# InverterControl.net
KiCad netlist of a schematic drawn in EAGLE
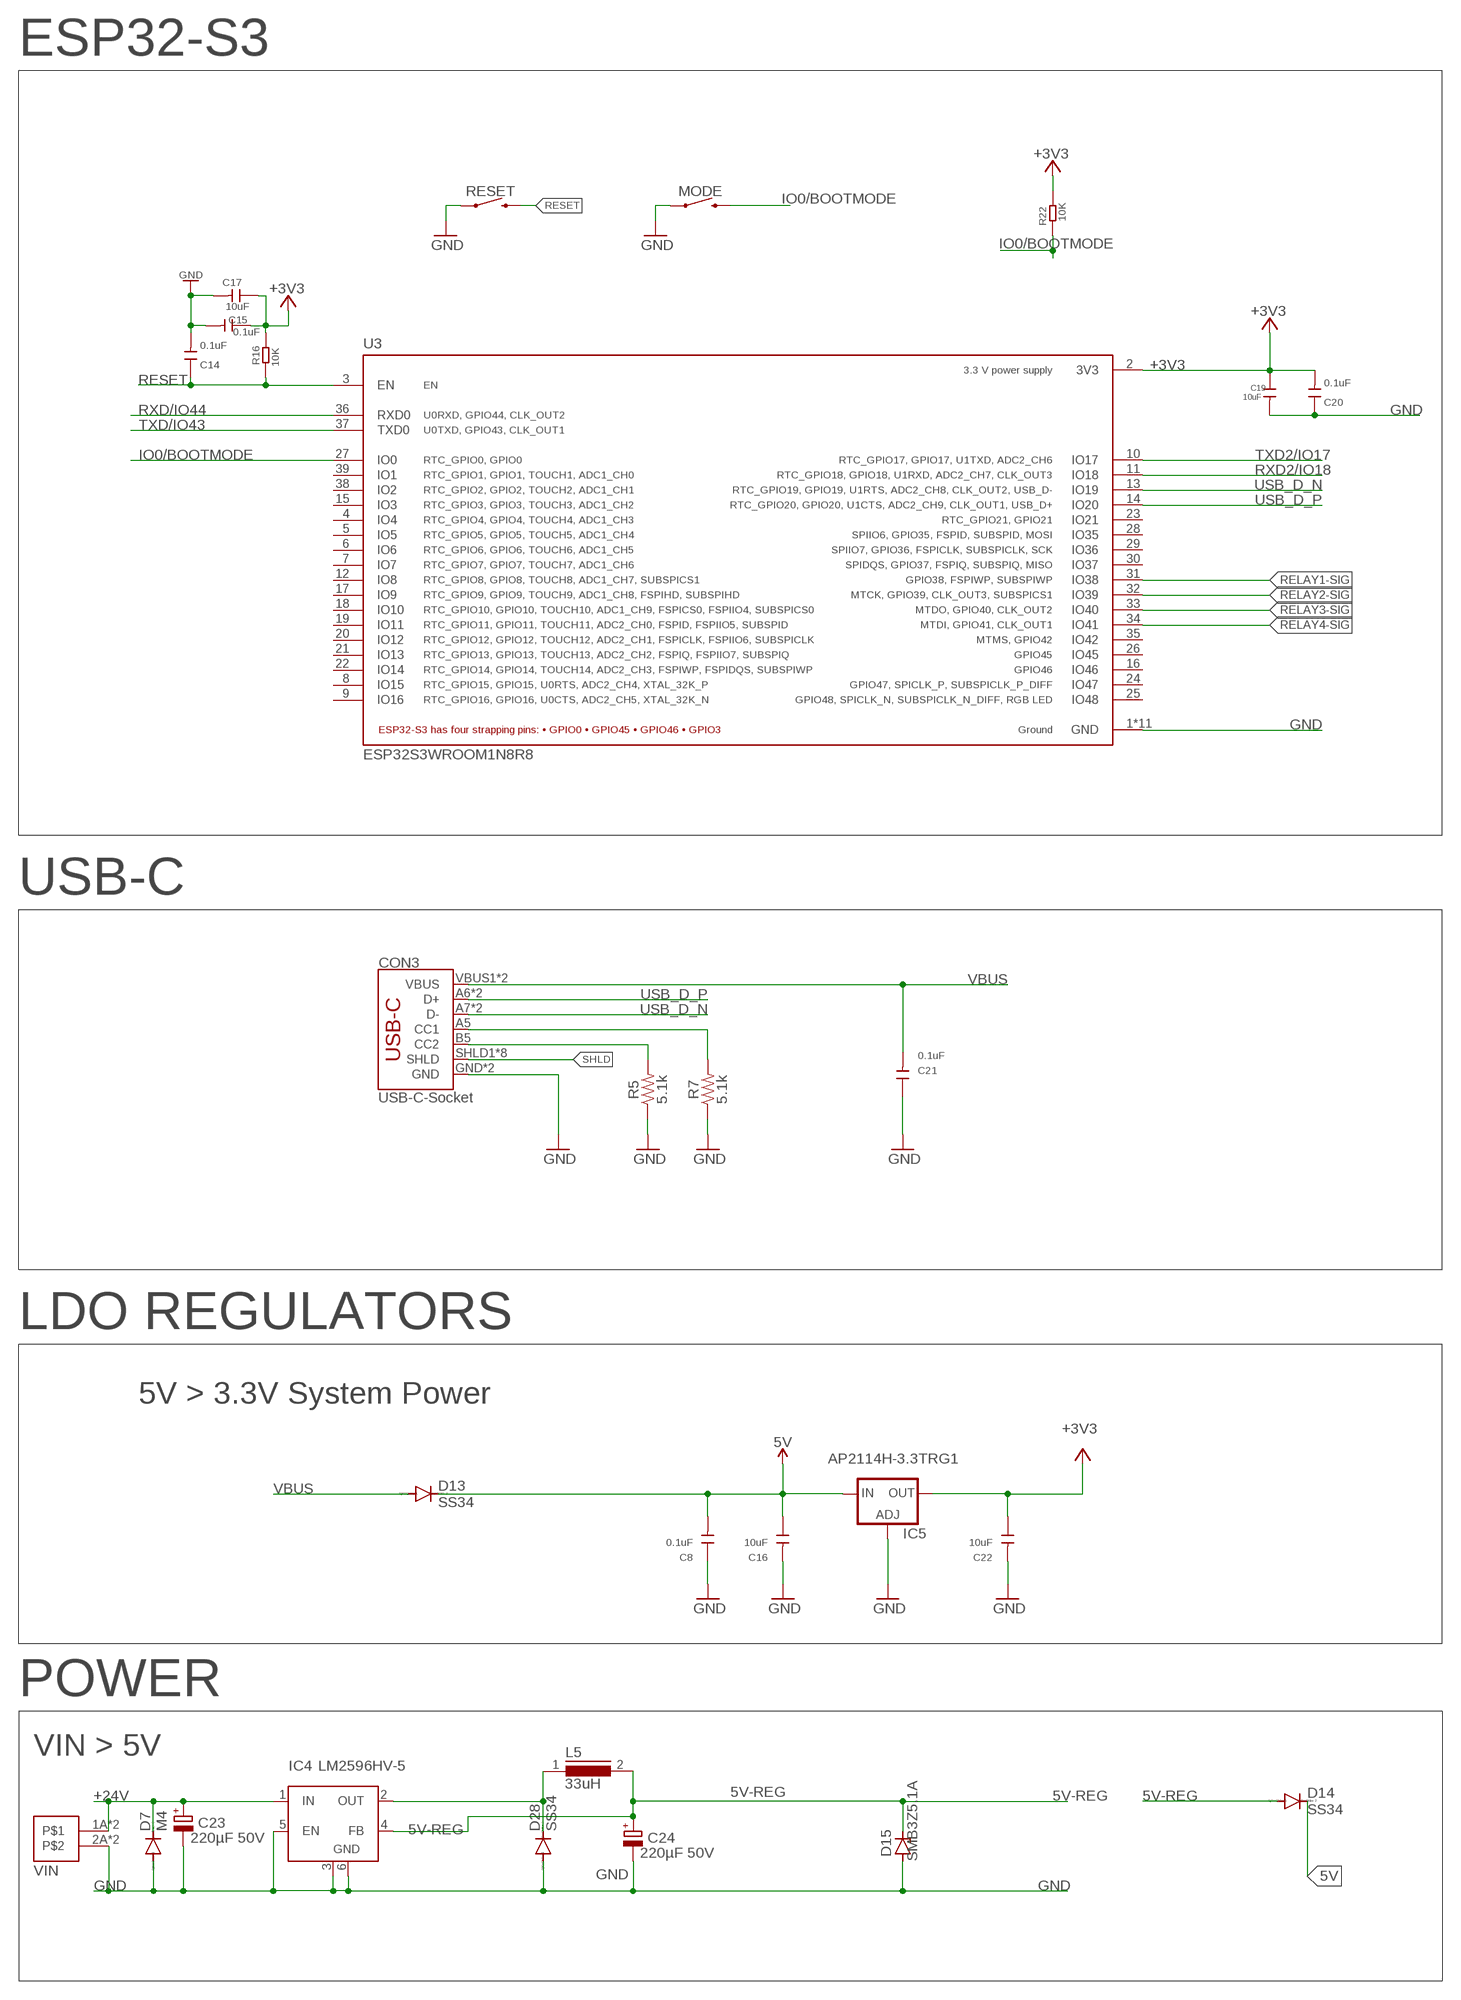
[diagram p0: schematic, sheet 1, part 1 of 2]
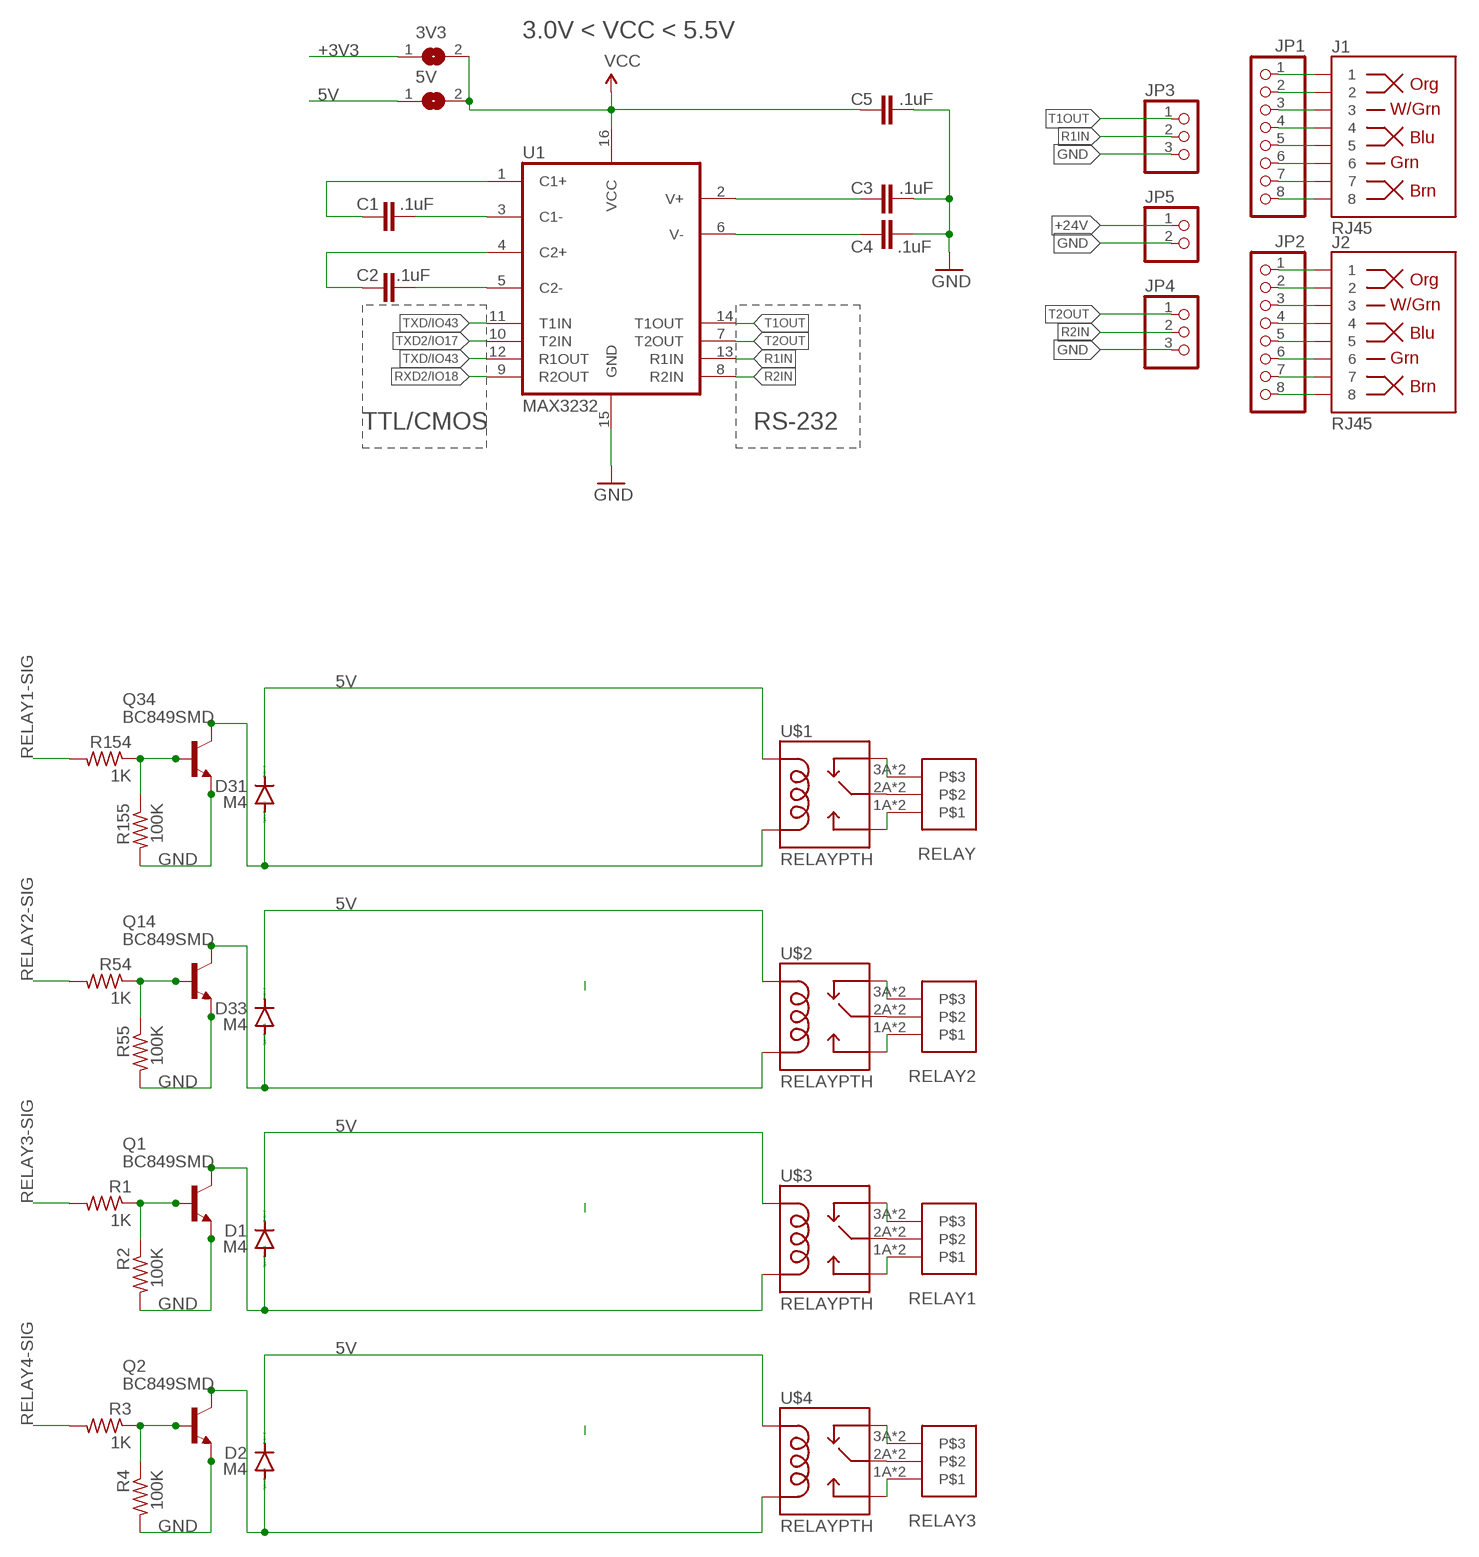
[diagram p1: schematic, sheet 1, part 2 of 2]

(export (version "E")
  (design (tool "Eeschema 10.0.6"))
  (components
    (comp (ref "3V3") (value "SJ") (footprint "eagle-import:SJ") (libsource (lib "eagle-import") (part "SJ")))
    (comp (ref "5V") (value "SJ") (footprint "eagle-import:SJ") (libsource (lib "eagle-import") (part "SJ")))
    (comp (ref "C1")
      (value ".1uF")
      (footprint "eagle-import:0603-CAP")
      (fields (field (name "PROD_ID") "CAP-00810"))
      (libsource (lib "eagle-import") (part "0.1UF-25V(+80/-20%)(0603)"))
    )
    (comp (ref "C2")
      (value ".1uF")
      (footprint "eagle-import:0603-CAP")
      (fields (field (name "PROD_ID") "CAP-00810"))
      (libsource (lib "eagle-import") (part "0.1UF-25V(+80/-20%)(0603)"))
    )
    (comp (ref "C3")
      (value ".1uF")
      (footprint "eagle-import:0603-CAP")
      (fields (field (name "PROD_ID") "CAP-00810"))
      (libsource (lib "eagle-import") (part "0.1UF-25V(+80/-20%)(0603)"))
    )
    (comp (ref "C4")
      (value ".1uF")
      (footprint "eagle-import:0603-CAP")
      (fields (field (name "PROD_ID") "CAP-00810"))
      (libsource (lib "eagle-import") (part "0.1UF-25V(+80/-20%)(0603)"))
    )
    (comp (ref "C5")
      (value ".1uF")
      (footprint "eagle-import:0603-CAP")
      (fields (field (name "PROD_ID") "CAP-00810"))
      (libsource (lib "eagle-import") (part "0.1UF-25V(+80/-20%)(0603)"))
    )
    (comp (ref "C8")
      (value "0.1uF")
      (footprint "eagle-import:DISCRETE_C1206")
      (libsource (lib "eagle-import") (part "DISCRETE_C-1206"))
    )
    (comp (ref "C14")
      (value "0.1uF")
      (footprint "eagle-import:DISCRETE_C1206")
      (libsource (lib "eagle-import") (part "DISCRETE_C-1206"))
    )
    (comp (ref "C15")
      (value "0.1uF")
      (footprint "eagle-import:DISCRETE_C1206")
      (libsource (lib "eagle-import") (part "DISCRETE_C-1206"))
    )
    (comp (ref "C16")
      (value "10uF")
      (footprint "eagle-import:C1206")
      (libsource (lib "eagle-import") (part "C-1206"))
    )
    (comp (ref "C17")
      (value "10uF")
      (footprint "eagle-import:DISCRETE_C1206")
      (libsource (lib "eagle-import") (part "DISCRETE_C-1206"))
    )
    (comp (ref "C19")
      (value "10uF")
      (footprint "eagle-import:C1206")
      (libsource (lib "eagle-import") (part "C-1206"))
    )
    (comp (ref "C20")
      (value "0.1uF")
      (footprint "eagle-import:DISCRETE_C1206")
      (libsource (lib "eagle-import") (part "DISCRETE_C-1206"))
    )
    (comp (ref "C21")
      (value "0.1uF")
      (footprint "eagle-import:DISCRETE_C1206")
      (libsource (lib "eagle-import") (part "DISCRETE_C-1206"))
    )
    (comp (ref "C22")
      (value "10uF")
      (footprint "eagle-import:C1206")
      (libsource (lib "eagle-import") (part "C-1206"))
    )
    (comp (ref "C23")
      (value "220µF 50V")
      (footprint "eagle-import:PANASONIC_E")
      (libsource (lib "eagle-import") (part "CPOL-EUE"))
    )
    (comp (ref "C24")
      (value "220µF 50V")
      (footprint "eagle-import:PANASONIC_E")
      (libsource (lib "eagle-import") (part "CPOL-EUE"))
    )
    (comp (ref "CON3")
      (value "USB-C-Socket")
      (footprint "eagle-import:USB-C-16P")
      (libsource (lib "eagle-import") (part "USB_C16PIN"))
    )
    (comp (ref "D1")
      (value "M4")
      (footprint "eagle-import:DO-214AC")
      (libsource (lib "eagle-import") (part "DIODE-DO-214AC"))
    )
    (comp (ref "D2")
      (value "M4")
      (footprint "eagle-import:DO-214AC")
      (libsource (lib "eagle-import") (part "DIODE-DO-214AC"))
    )
    (comp (ref "D7")
      (value "M4")
      (footprint "eagle-import:DO-214AC")
      (libsource (lib "eagle-import") (part "DIODE-DO-214AC"))
    )
    (comp (ref "D13")
      (value "SS34")
      (footprint "eagle-import:DO-214AC")
      (libsource (lib "eagle-import") (part "DIODE-DO-214AC"))
    )
    (comp (ref "D14")
      (value "SS34")
      (footprint "eagle-import:SMB")
      (libsource (lib "eagle-import") (part "DIODE-SMB"))
    )
    (comp (ref "D15")
      (value "SMB3Z5.1A")
      (footprint "eagle-import:SMB")
      (libsource (lib "eagle-import") (part "ZENER-DIODESMB"))
    )
    (comp (ref "D28")
      (value "SS34")
      (footprint "eagle-import:SMB")
      (libsource (lib "eagle-import") (part "DIODE-SMB"))
    )
    (comp (ref "D31")
      (value "M4")
      (footprint "eagle-import:DO-214AC")
      (libsource (lib "eagle-import") (part "DIODE-DO-214AC"))
    )
    (comp (ref "D33")
      (value "M4")
      (footprint "eagle-import:DO-214AC")
      (libsource (lib "eagle-import") (part "DIODE-DO-214AC"))
    )
    (comp (ref "IC4")
      (value "LM2596HV-5")
      (footprint "eagle-import:TO263-5")
      (libsource (lib "eagle-import") (part "LM2596S"))
    )
    (comp (ref "IC5")
      (value "AP2114H-3.3TRG1")
      (footprint "eagle-import:SOT223")
      (libsource (lib "eagle-import") (part "LD117A?S33TR"))
    )
    (comp (ref "J1")
      (value "RJ45")
      (footprint "eagle-import:RJ45-8")
      (libsource (lib "eagle-import") (part "RJ45-8"))
    )
    (comp (ref "J2")
      (value "RJ45")
      (footprint "eagle-import:RJ45-8")
      (libsource (lib "eagle-import") (part "RJ45-8"))
    )
    (comp (ref "JP1")
      (value "PINHD-1X8")
      (footprint "eagle-import:1X08")
      (libsource (lib "eagle-import") (part "PINHD-1X8"))
    )
    (comp (ref "JP2")
      (value "PINHD-1X8")
      (footprint "eagle-import:1X08")
      (libsource (lib "eagle-import") (part "PINHD-1X8"))
    )
    (comp (ref "JP3")
      (value "PINHD-1X3")
      (footprint "eagle-import:1X03")
      (libsource (lib "eagle-import") (part "PINHD-1X3"))
    )
    (comp (ref "JP4")
      (value "PINHD-1X3")
      (footprint "eagle-import:1X03")
      (libsource (lib "eagle-import") (part "PINHD-1X3"))
    )
    (comp (ref "JP5")
      (value "PINHD-1X2")
      (footprint "eagle-import:1X02")
      (libsource (lib "eagle-import") (part "PINHD-1X2"))
    )
    (comp (ref "L5")
      (value "33uH")
      (footprint "eagle-import:DR127")
      (libsource (lib "eagle-import") (part "DR127"))
    )
    (comp (ref "MODE")
      (value "MOMENTARY-SWITCH-SPST-PTH-6.0MM")
      (footprint "eagle-import:TACTILE_SWITCH_PTH_6.0MM")
      (libsource (lib "eagle-import") (part "MOMENTARY-SWITCH-SPST-PTH-6.0MM"))
    )
    (comp (ref "Q1")
      (value "BC849SMD")
      (footprint "eagle-import:SOT23-BEC")
      (libsource (lib "eagle-import") (part "BC849SMD"))
    )
    (comp (ref "Q2")
      (value "BC849SMD")
      (footprint "eagle-import:SOT23-BEC")
      (libsource (lib "eagle-import") (part "BC849SMD"))
    )
    (comp (ref "Q14")
      (value "BC849SMD")
      (footprint "eagle-import:SOT23-BEC")
      (libsource (lib "eagle-import") (part "BC849SMD"))
    )
    (comp (ref "Q34")
      (value "BC849SMD")
      (footprint "eagle-import:SOT23-BEC")
      (libsource (lib "eagle-import") (part "BC849SMD"))
    )
    (comp (ref "R1")
      (value "1K")
      (footprint "eagle-import:R1206")
      (libsource (lib "eagle-import") (part "R-US_R1206"))
    )
    (comp (ref "R2")
      (value "100K")
      (footprint "eagle-import:R1206")
      (libsource (lib "eagle-import") (part "R-US_R1206"))
    )
    (comp (ref "R3")
      (value "1K")
      (footprint "eagle-import:R1206")
      (libsource (lib "eagle-import") (part "R-US_R1206"))
    )
    (comp (ref "R4")
      (value "100K")
      (footprint "eagle-import:R1206")
      (libsource (lib "eagle-import") (part "R-US_R1206"))
    )
    (comp (ref "R5")
      (value "5.1k")
      (footprint "eagle-import:0603@1")
      (libsource (lib "eagle-import") (part "5.1KOHM5.1KOHM-0603-1/10W-1%"))
    )
    (comp (ref "R7")
      (value "5.1k")
      (footprint "eagle-import:0603@1")
      (libsource (lib "eagle-import") (part "5.1KOHM5.1KOHM-0603-1/10W-1%"))
    )
    (comp (ref "R16")
      (value "10K")
      (footprint "eagle-import:R1206")
      (libsource (lib "eagle-import") (part "R-1206"))
    )
    (comp (ref "R22")
      (value "10K")
      (footprint "eagle-import:R1206")
      (libsource (lib "eagle-import") (part "R-1206"))
    )
    (comp (ref "R54")
      (value "1K")
      (footprint "eagle-import:R1206")
      (libsource (lib "eagle-import") (part "R-US_R1206"))
    )
    (comp (ref "R55")
      (value "100K")
      (footprint "eagle-import:R1206")
      (libsource (lib "eagle-import") (part "R-US_R1206"))
    )
    (comp (ref "R154")
      (value "1K")
      (footprint "eagle-import:R1206")
      (libsource (lib "eagle-import") (part "R-US_R1206"))
    )
    (comp (ref "R155")
      (value "100K")
      (footprint "eagle-import:R1206")
      (libsource (lib "eagle-import") (part "R-US_R1206"))
    )
    (comp (ref "RELAY")
      (value "WJ212R-THR-3.5-3")
      (footprint "eagle-import:WJ212R-THR-3.5-3")
      (libsource (lib "eagle-import") (part "WJ212R-THR-3.5-3"))
    )
    (comp (ref "RELAY1")
      (value "WJ212R-THR-3.5-3")
      (footprint "eagle-import:WJ212R-THR-3.5-3")
      (libsource (lib "eagle-import") (part "WJ212R-THR-3.5-3"))
    )
    (comp (ref "RELAY2")
      (value "WJ212R-THR-3.5-3")
      (footprint "eagle-import:WJ212R-THR-3.5-3")
      (libsource (lib "eagle-import") (part "WJ212R-THR-3.5-3"))
    )
    (comp (ref "RELAY3")
      (value "WJ212R-THR-3.5-3")
      (footprint "eagle-import:WJ212R-THR-3.5-3")
      (libsource (lib "eagle-import") (part "WJ212R-THR-3.5-3"))
    )
    (comp (ref "RESET")
      (value "MOMENTARY-SWITCH-SPST-PTH-6.0MM")
      (footprint "eagle-import:TACTILE_SWITCH_PTH_6.0MM")
      (libsource (lib "eagle-import") (part "MOMENTARY-SWITCH-SPST-PTH-6.0MM"))
    )
    (comp (ref "U$1")
      (value "RELAYPTH")
      (footprint "eagle-import:SRD-05VDC-SL-C")
      (libsource (lib "eagle-import") (part "RELAYPTH"))
    )
    (comp (ref "U$2")
      (value "RELAYPTH")
      (footprint "eagle-import:SRD-05VDC-SL-C")
      (libsource (lib "eagle-import") (part "RELAYPTH"))
    )
    (comp (ref "U$3")
      (value "RELAYPTH")
      (footprint "eagle-import:SRD-05VDC-SL-C")
      (libsource (lib "eagle-import") (part "RELAYPTH"))
    )
    (comp (ref "U$4")
      (value "RELAYPTH")
      (footprint "eagle-import:SRD-05VDC-SL-C")
      (libsource (lib "eagle-import") (part "RELAYPTH"))
    )
    (comp (ref "U1")
      (value "MAX3232")
      (footprint "eagle-import:SO016")
      (libsource (lib "eagle-import") (part "MAX232SOIC16"))
    )
    (comp (ref "U3")
      (value "ESP32S3WROOM1N8R8")
      (footprint "eagle-import:XCVR_ESP32S3WROOM1N8R8")
      (fields (field (name "MF") "Espressif Systems"))
      (libsource (lib "eagle-import") (part "ESP32S3WROOM1N8R8"))
    )
    (comp (ref "VIN")
      (value "WJ212R-THR-3.5-2")
      (footprint "eagle-import:WJ212R-THR-3.5-2")
      (libsource (lib "eagle-import") (part "WJ212R-THR-3.5-2"))
    )
  )
  (nets
    (net (code "1") (name "+3V3") (class "Default")
      (node (ref "3V3") (pin "1") (pinfunction "1_1") (pintype "passive"))
      (node (ref "C15") (pin "1") (pinfunction "1_1") (pintype "passive"))
      (node (ref "C17") (pin "1") (pinfunction "1_1") (pintype "passive"))
      (node (ref "C19") (pin "1") (pinfunction "1_1") (pintype "passive"))
      (node (ref "C20") (pin "2") (pinfunction "2_2") (pintype "passive"))
      (node (ref "C22") (pin "1") (pinfunction "1_1") (pintype "passive"))
      (node (ref "IC5") (pin "4") (pinfunction "OUT_4") (pintype "passive"))
      (node (ref "R16") (pin "2") (pinfunction "2_2") (pintype "passive"))
      (node (ref "R22") (pin "2") (pinfunction "2_2") (pintype "passive"))
      (node (ref "U3") (pin "2") (pinfunction "3V3_2") (pintype "power_in"))
    )
    (net (code "2") (name "+24V") (class "Default")
      (node (ref "C23") (pin "+") (pinfunction "+_+") (pintype "passive"))
      (node (ref "D7") (pin "C") (pinfunction "C_C") (pintype "passive"))
      (node (ref "IC4") (pin "1") (pinfunction "IN_1") (pintype "input"))
      (node (ref "JP5") (pin "1") (pinfunction "1_1") (pintype "passive"))
      (node (ref "VIN") (pin "1A") (pinfunction "P$1_1A") (pintype "bidirectional"))
      (node (ref "VIN") (pin "1B") (pinfunction "P$1_1B") (pintype "bidirectional"))
    )
    (net (code "3") (name "/5V-REG") (class "Default")
      (node (ref "C24") (pin "+") (pinfunction "+_+") (pintype "passive"))
      (node (ref "D14") (pin "A") (pinfunction "A_A") (pintype "passive"))
      (node (ref "D15") (pin "C") (pinfunction "C_C") (pintype "passive"))
      (node (ref "IC4") (pin "4") (pinfunction "FB_4") (pintype "input"))
      (node (ref "L5") (pin "2") (pinfunction "2_2") (pintype "passive"))
    )
    (net (code "4") (name "/IO0{slash}BOOTMODE") (class "Default")
      (node (ref "MODE") (pin "3") (pinfunction "2_3") (pintype "passive"))
      (node (ref "R22") (pin "1") (pinfunction "1_1") (pintype "passive"))
      (node (ref "U3") (pin "27") (pinfunction "IO0_27") (pintype "bidirectional"))
    )
    (net (code "5") (name "/RXD{slash}IO44") (class "Default")
      (node (ref "U3") (pin "36") (pinfunction "RXD0_36") (pintype "bidirectional"))
    )
    (net (code "6") (name "/USB_D_N") (class "Default")
      (node (ref "CON3") (pin "A7") (pinfunction "D-_A7") (pintype "bidirectional"))
      (node (ref "CON3") (pin "B7") (pinfunction "D-_B7") (pintype "bidirectional"))
      (node (ref "U3") (pin "13") (pinfunction "IO19_13") (pintype "bidirectional"))
    )
    (net (code "7") (name "/USB_D_P") (class "Default")
      (node (ref "CON3") (pin "A6") (pinfunction "D+_A6") (pintype "bidirectional"))
      (node (ref "CON3") (pin "B6") (pinfunction "D+_B6") (pintype "bidirectional"))
      (node (ref "U3") (pin "14") (pinfunction "IO20_14") (pintype "bidirectional"))
    )
    (net (code "8") (name "/VBUS") (class "Default")
      (node (ref "C21") (pin "2") (pinfunction "2_2") (pintype "passive"))
      (node (ref "CON3") (pin "VBUS1") (pinfunction "VBUS_VBUS1") (pintype "bidirectional"))
      (node (ref "CON3") (pin "VBUS2") (pinfunction "VBUS_VBUS2") (pintype "bidirectional"))
      (node (ref "D13") (pin "A") (pinfunction "A_A") (pintype "passive"))
    )
    (net (code "9") (name "5V") (class "Default")
      (node (ref "5V") (pin "1") (pinfunction "1_1") (pintype "passive"))
      (node (ref "C16") (pin "1") (pinfunction "1_1") (pintype "passive"))
      (node (ref "C8") (pin "2") (pinfunction "2_2") (pintype "passive"))
      (node (ref "D1") (pin "C") (pinfunction "C_C") (pintype "passive"))
      (node (ref "D13") (pin "C") (pinfunction "C_C") (pintype "passive"))
      (node (ref "D14") (pin "C") (pinfunction "C_C") (pintype "passive"))
      (node (ref "D2") (pin "C") (pinfunction "C_C") (pintype "passive"))
      (node (ref "D31") (pin "C") (pinfunction "C_C") (pintype "passive"))
      (node (ref "D33") (pin "C") (pinfunction "C_C") (pintype "passive"))
      (node (ref "IC5") (pin "3") (pinfunction "IN_3") (pintype "input"))
      (node (ref "U$1") (pin "COIL1") (pinfunction "COIL1_COIL1") (pintype "bidirectional"))
      (node (ref "U$2") (pin "COIL1") (pinfunction "COIL1_COIL1") (pintype "bidirectional"))
      (node (ref "U$3") (pin "COIL1") (pinfunction "COIL1_COIL1") (pintype "bidirectional"))
      (node (ref "U$4") (pin "COIL1") (pinfunction "COIL1_COIL1") (pintype "bidirectional"))
    )
    (net (code "10") (name "GND") (class "Default")
      (node (ref "C14") (pin "2") (pinfunction "2_2") (pintype "passive"))
      (node (ref "C15") (pin "2") (pinfunction "2_2") (pintype "passive"))
      (node (ref "C16") (pin "2") (pinfunction "2_2") (pintype "passive"))
      (node (ref "C17") (pin "2") (pinfunction "2_2") (pintype "passive"))
      (node (ref "C19") (pin "2") (pinfunction "2_2") (pintype "passive"))
      (node (ref "C20") (pin "1") (pinfunction "1_1") (pintype "passive"))
      (node (ref "C21") (pin "1") (pinfunction "1_1") (pintype "passive"))
      (node (ref "C22") (pin "2") (pinfunction "2_2") (pintype "passive"))
      (node (ref "C23") (pin "-") (pinfunction "-_-") (pintype "passive"))
      (node (ref "C24") (pin "-") (pinfunction "-_-") (pintype "passive"))
      (node (ref "C3") (pin "2") (pinfunction "2_2") (pintype "passive"))
      (node (ref "C4") (pin "2") (pinfunction "2_2") (pintype "passive"))
      (node (ref "C5") (pin "2") (pinfunction "2_2") (pintype "passive"))
      (node (ref "C8") (pin "1") (pinfunction "1_1") (pintype "passive"))
      (node (ref "CON3") (pin "GND") (pinfunction "GND_GND") (pintype "bidirectional"))
      (node (ref "CON3") (pin "GND2") (pinfunction "GND_GND2") (pintype "bidirectional"))
      (node (ref "D15") (pin "A") (pinfunction "A_A") (pintype "passive"))
      (node (ref "D28") (pin "A") (pinfunction "A_A") (pintype "passive"))
      (node (ref "D7") (pin "A") (pinfunction "A_A") (pintype "passive"))
      (node (ref "IC4") (pin "3") (pinfunction "GND_3") (pintype "power_in"))
      (node (ref "IC4") (pin "5") (pinfunction "EN_5") (pintype "input"))
      (node (ref "IC4") (pin "6") (pinfunction "GND_6") (pintype "power_in"))
      (node (ref "IC5") (pin "1") (pinfunction "ADJ_1") (pintype "input"))
      (node (ref "JP3") (pin "3") (pinfunction "3_3") (pintype "passive"))
      (node (ref "JP4") (pin "3") (pinfunction "3_3") (pintype "passive"))
      (node (ref "JP5") (pin "2") (pinfunction "2_2") (pintype "passive"))
      (node (ref "MODE") (pin "1") (pinfunction "1_1") (pintype "passive"))
      (node (ref "Q1") (pin "E") (pinfunction "E_E") (pintype "passive"))
      (node (ref "Q14") (pin "E") (pinfunction "E_E") (pintype "passive"))
      (node (ref "Q2") (pin "E") (pinfunction "E_E") (pintype "passive"))
      (node (ref "Q34") (pin "E") (pinfunction "E_E") (pintype "passive"))
      (node (ref "R155") (pin "2") (pinfunction "2_2") (pintype "passive"))
      (node (ref "R2") (pin "2") (pinfunction "2_2") (pintype "passive"))
      (node (ref "R4") (pin "2") (pinfunction "2_2") (pintype "passive"))
      (node (ref "R5") (pin "1") (pinfunction "1_1") (pintype "passive"))
      (node (ref "R55") (pin "2") (pinfunction "2_2") (pintype "passive"))
      (node (ref "R7") (pin "1") (pinfunction "1_1") (pintype "passive"))
      (node (ref "RESET") (pin "1") (pinfunction "1_1") (pintype "passive"))
      (node (ref "U1") (pin "15") (pinfunction "GND_15") (pintype "bidirectional"))
      (node (ref "U3") (pin "1") (pinfunction "GND_1") (pintype "power_in"))
      (node (ref "U3") (pin "40") (pinfunction "GND_40") (pintype "power_in"))
      (node (ref "U3") (pin "41_1") (pinfunction "GND_41_1") (pintype "power_in"))
      (node (ref "U3") (pin "41_2") (pinfunction "GND_41_2") (pintype "power_in"))
      (node (ref "U3") (pin "41_3") (pinfunction "GND_41_3") (pintype "power_in"))
      (node (ref "U3") (pin "41_4") (pinfunction "GND_41_4") (pintype "power_in"))
      (node (ref "U3") (pin "41_5") (pinfunction "GND_41_5") (pintype "power_in"))
      (node (ref "U3") (pin "41_6") (pinfunction "GND_41_6") (pintype "power_in"))
      (node (ref "U3") (pin "41_7") (pinfunction "GND_41_7") (pintype "power_in"))
      (node (ref "U3") (pin "41_8") (pinfunction "GND_41_8") (pintype "power_in"))
      (node (ref "U3") (pin "41_9") (pinfunction "GND_41_9") (pintype "power_in"))
      (node (ref "VIN") (pin "2A") (pinfunction "P$2_2A") (pintype "bidirectional"))
      (node (ref "VIN") (pin "2B") (pinfunction "P$2_2B") (pintype "bidirectional"))
    )
    (net (code "11") (name "Net-(CON3-CC1)") (class "Default")
      (node (ref "CON3") (pin "A5") (pinfunction "CC1_A5") (pintype "bidirectional"))
      (node (ref "R7") (pin "2") (pinfunction "2_2") (pintype "passive"))
    )
    (net (code "12") (name "Net-(CON3-CC2)") (class "Default")
      (node (ref "CON3") (pin "B5") (pinfunction "CC2_B5") (pintype "bidirectional"))
      (node (ref "R5") (pin "2") (pinfunction "2_2") (pintype "passive"))
    )
    (net (code "13") (name "Net-(D1-PadA)") (class "Default")
      (node (ref "D1") (pin "A") (pinfunction "A_A") (pintype "passive"))
      (node (ref "Q1") (pin "C") (pinfunction "C_C") (pintype "passive"))
      (node (ref "U$3") (pin "COIL0") (pinfunction "COIL0_COIL0") (pintype "bidirectional"))
    )
    (net (code "14") (name "Net-(D2-PadA)") (class "Default")
      (node (ref "D2") (pin "A") (pinfunction "A_A") (pintype "passive"))
      (node (ref "Q2") (pin "C") (pinfunction "C_C") (pintype "passive"))
      (node (ref "U$4") (pin "COIL0") (pinfunction "COIL0_COIL0") (pintype "bidirectional"))
    )
    (net (code "15") (name "Net-(D31-PadA)") (class "Default")
      (node (ref "D31") (pin "A") (pinfunction "A_A") (pintype "passive"))
      (node (ref "Q34") (pin "C") (pinfunction "C_C") (pintype "passive"))
      (node (ref "U$1") (pin "COIL0") (pinfunction "COIL0_COIL0") (pintype "bidirectional"))
    )
    (net (code "16") (name "Net-(D33-PadA)") (class "Default")
      (node (ref "D33") (pin "A") (pinfunction "A_A") (pintype "passive"))
      (node (ref "Q14") (pin "C") (pinfunction "C_C") (pintype "passive"))
      (node (ref "U$2") (pin "COIL0") (pinfunction "COIL0_COIL0") (pintype "bidirectional"))
    )
    (net (code "17") (name "Net-(IC4-OUT)") (class "Default")
      (node (ref "D28") (pin "C") (pinfunction "C_C") (pintype "passive"))
      (node (ref "IC4") (pin "2") (pinfunction "OUT_2") (pintype "output"))
      (node (ref "L5") (pin "1") (pinfunction "1_1") (pintype "passive"))
    )
    (net (code "18") (name "Net-(J1-Pad1)") (class "Default")
      (node (ref "J1") (pin "1") (pinfunction "1_1") (pintype "bidirectional"))
      (node (ref "JP1") (pin "1") (pinfunction "1_1") (pintype "passive"))
    )
    (net (code "19") (name "Net-(J1-Pad2)") (class "Default")
      (node (ref "J1") (pin "2") (pinfunction "2_2") (pintype "bidirectional"))
      (node (ref "JP1") (pin "2") (pinfunction "2_2") (pintype "passive"))
    )
    (net (code "20") (name "Net-(J1-Pad3)") (class "Default")
      (node (ref "J1") (pin "3") (pinfunction "3_3") (pintype "bidirectional"))
      (node (ref "JP1") (pin "3") (pinfunction "3_3") (pintype "passive"))
    )
    (net (code "21") (name "Net-(J1-Pad4)") (class "Default")
      (node (ref "J1") (pin "4") (pinfunction "4_4") (pintype "bidirectional"))
      (node (ref "JP1") (pin "4") (pinfunction "4_4") (pintype "passive"))
    )
    (net (code "22") (name "Net-(J1-Pad5)") (class "Default")
      (node (ref "J1") (pin "5") (pinfunction "5_5") (pintype "bidirectional"))
      (node (ref "JP1") (pin "5") (pinfunction "5_5") (pintype "passive"))
    )
    (net (code "23") (name "Net-(J1-Pad6)") (class "Default")
      (node (ref "J1") (pin "6") (pinfunction "6_6") (pintype "bidirectional"))
      (node (ref "JP1") (pin "6") (pinfunction "6_6") (pintype "passive"))
    )
    (net (code "24") (name "Net-(J1-Pad7)") (class "Default")
      (node (ref "J1") (pin "7") (pinfunction "7_7") (pintype "bidirectional"))
      (node (ref "JP1") (pin "7") (pinfunction "7_7") (pintype "passive"))
    )
    (net (code "25") (name "Net-(J1-Pad8)") (class "Default")
      (node (ref "J1") (pin "8") (pinfunction "8_8") (pintype "bidirectional"))
      (node (ref "JP1") (pin "8") (pinfunction "8_8") (pintype "passive"))
    )
    (net (code "26") (name "Net-(J2-Pad1)") (class "Default")
      (node (ref "J2") (pin "1") (pinfunction "1_1") (pintype "bidirectional"))
      (node (ref "JP2") (pin "1") (pinfunction "1_1") (pintype "passive"))
    )
    (net (code "27") (name "Net-(J2-Pad2)") (class "Default")
      (node (ref "J2") (pin "2") (pinfunction "2_2") (pintype "bidirectional"))
      (node (ref "JP2") (pin "2") (pinfunction "2_2") (pintype "passive"))
    )
    (net (code "28") (name "Net-(J2-Pad3)") (class "Default")
      (node (ref "J2") (pin "3") (pinfunction "3_3") (pintype "bidirectional"))
      (node (ref "JP2") (pin "3") (pinfunction "3_3") (pintype "passive"))
    )
    (net (code "29") (name "Net-(J2-Pad4)") (class "Default")
      (node (ref "J2") (pin "4") (pinfunction "4_4") (pintype "bidirectional"))
      (node (ref "JP2") (pin "4") (pinfunction "4_4") (pintype "passive"))
    )
    (net (code "30") (name "Net-(J2-Pad5)") (class "Default")
      (node (ref "J2") (pin "5") (pinfunction "5_5") (pintype "bidirectional"))
      (node (ref "JP2") (pin "5") (pinfunction "5_5") (pintype "passive"))
    )
    (net (code "31") (name "Net-(J2-Pad6)") (class "Default")
      (node (ref "J2") (pin "6") (pinfunction "6_6") (pintype "bidirectional"))
      (node (ref "JP2") (pin "6") (pinfunction "6_6") (pintype "passive"))
    )
    (net (code "32") (name "Net-(J2-Pad7)") (class "Default")
      (node (ref "J2") (pin "7") (pinfunction "7_7") (pintype "bidirectional"))
      (node (ref "JP2") (pin "7") (pinfunction "7_7") (pintype "passive"))
    )
    (net (code "33") (name "Net-(J2-Pad8)") (class "Default")
      (node (ref "J2") (pin "8") (pinfunction "8_8") (pintype "bidirectional"))
      (node (ref "JP2") (pin "8") (pinfunction "8_8") (pintype "passive"))
    )
    (net (code "34") (name "Net-(Q1-PadB)") (class "Default")
      (node (ref "Q1") (pin "B") (pinfunction "B_B") (pintype "passive"))
      (node (ref "R1") (pin "1") (pinfunction "1_1") (pintype "passive"))
      (node (ref "R2") (pin "1") (pinfunction "1_1") (pintype "passive"))
    )
    (net (code "35") (name "Net-(Q2-PadB)") (class "Default")
      (node (ref "Q2") (pin "B") (pinfunction "B_B") (pintype "passive"))
      (node (ref "R3") (pin "1") (pinfunction "1_1") (pintype "passive"))
      (node (ref "R4") (pin "1") (pinfunction "1_1") (pintype "passive"))
    )
    (net (code "36") (name "Net-(Q14-PadB)") (class "Default")
      (node (ref "Q14") (pin "B") (pinfunction "B_B") (pintype "passive"))
      (node (ref "R54") (pin "1") (pinfunction "1_1") (pintype "passive"))
      (node (ref "R55") (pin "1") (pinfunction "1_1") (pintype "passive"))
    )
    (net (code "37") (name "Net-(Q34-PadB)") (class "Default")
      (node (ref "Q34") (pin "B") (pinfunction "B_B") (pintype "passive"))
      (node (ref "R154") (pin "1") (pinfunction "1_1") (pintype "passive"))
      (node (ref "R155") (pin "1") (pinfunction "1_1") (pintype "passive"))
    )
    (net (code "38") (name "Net-(RELAY-P$1-Pad1A)") (class "Default")
      (node (ref "RELAY") (pin "1A") (pinfunction "P$1_1A") (pintype "bidirectional"))
      (node (ref "RELAY") (pin "1B") (pinfunction "P$1_1B") (pintype "bidirectional"))
      (node (ref "U$1") (pin "SWOPEN") (pinfunction "SWOPEN_SWOPEN") (pintype "bidirectional"))
    )
    (net (code "39") (name "Net-(RELAY-P$2-Pad2A)") (class "Default")
      (node (ref "RELAY") (pin "2A") (pinfunction "P$2_2A") (pintype "bidirectional"))
      (node (ref "RELAY") (pin "2B") (pinfunction "P$2_2B") (pintype "bidirectional"))
      (node (ref "U$1") (pin "SWCOMMON") (pinfunction "SWCOMMON_SWCOMMON") (pintype "bidirectional"))
    )
    (net (code "40") (name "Net-(RELAY1-P$1-Pad1A)") (class "Default")
      (node (ref "RELAY1") (pin "1A") (pinfunction "P$1_1A") (pintype "bidirectional"))
      (node (ref "RELAY1") (pin "1B") (pinfunction "P$1_1B") (pintype "bidirectional"))
      (node (ref "U$3") (pin "SWOPEN") (pinfunction "SWOPEN_SWOPEN") (pintype "bidirectional"))
    )
    (net (code "41") (name "Net-(RELAY1-P$2-Pad2A)") (class "Default")
      (node (ref "RELAY1") (pin "2A") (pinfunction "P$2_2A") (pintype "bidirectional"))
      (node (ref "RELAY1") (pin "2B") (pinfunction "P$2_2B") (pintype "bidirectional"))
      (node (ref "U$3") (pin "SWCOMMON") (pinfunction "SWCOMMON_SWCOMMON") (pintype "bidirectional"))
    )
    (net (code "42") (name "Net-(RELAY2-P$1-Pad1A)") (class "Default")
      (node (ref "RELAY2") (pin "1A") (pinfunction "P$1_1A") (pintype "bidirectional"))
      (node (ref "RELAY2") (pin "1B") (pinfunction "P$1_1B") (pintype "bidirectional"))
      (node (ref "U$2") (pin "SWOPEN") (pinfunction "SWOPEN_SWOPEN") (pintype "bidirectional"))
    )
    (net (code "43") (name "Net-(RELAY2-P$2-Pad2A)") (class "Default")
      (node (ref "RELAY2") (pin "2A") (pinfunction "P$2_2A") (pintype "bidirectional"))
      (node (ref "RELAY2") (pin "2B") (pinfunction "P$2_2B") (pintype "bidirectional"))
      (node (ref "U$2") (pin "SWCOMMON") (pinfunction "SWCOMMON_SWCOMMON") (pintype "bidirectional"))
    )
    (net (code "44") (name "Net-(RELAY3-P$1-Pad1A)") (class "Default")
      (node (ref "RELAY3") (pin "1A") (pinfunction "P$1_1A") (pintype "bidirectional"))
      (node (ref "RELAY3") (pin "1B") (pinfunction "P$1_1B") (pintype "bidirectional"))
      (node (ref "U$4") (pin "SWOPEN") (pinfunction "SWOPEN_SWOPEN") (pintype "bidirectional"))
    )
    (net (code "45") (name "Net-(RELAY3-P$2-Pad2A)") (class "Default")
      (node (ref "RELAY3") (pin "2A") (pinfunction "P$2_2A") (pintype "bidirectional"))
      (node (ref "RELAY3") (pin "2B") (pinfunction "P$2_2B") (pintype "bidirectional"))
      (node (ref "U$4") (pin "SWCOMMON") (pinfunction "SWCOMMON_SWCOMMON") (pintype "bidirectional"))
    )
    (net (code "46") (name "Net-(U$1-SWCLOSE)") (class "Default")
      (node (ref "RELAY") (pin "3A") (pinfunction "P$3_3A") (pintype "bidirectional"))
      (node (ref "RELAY") (pin "3B") (pinfunction "P$3_3B") (pintype "bidirectional"))
      (node (ref "U$1") (pin "SWCLOSED") (pinfunction "SWCLOSE_SWCLOSED") (pintype "bidirectional"))
    )
    (net (code "47") (name "Net-(U$2-SWCLOSE)") (class "Default")
      (node (ref "RELAY2") (pin "3A") (pinfunction "P$3_3A") (pintype "bidirectional"))
      (node (ref "RELAY2") (pin "3B") (pinfunction "P$3_3B") (pintype "bidirectional"))
      (node (ref "U$2") (pin "SWCLOSED") (pinfunction "SWCLOSE_SWCLOSED") (pintype "bidirectional"))
    )
    (net (code "48") (name "Net-(U$3-SWCLOSE)") (class "Default")
      (node (ref "RELAY1") (pin "3A") (pinfunction "P$3_3A") (pintype "bidirectional"))
      (node (ref "RELAY1") (pin "3B") (pinfunction "P$3_3B") (pintype "bidirectional"))
      (node (ref "U$3") (pin "SWCLOSED") (pinfunction "SWCLOSE_SWCLOSED") (pintype "bidirectional"))
    )
    (net (code "49") (name "Net-(U$4-SWCLOSE)") (class "Default")
      (node (ref "RELAY3") (pin "3A") (pinfunction "P$3_3A") (pintype "bidirectional"))
      (node (ref "RELAY3") (pin "3B") (pinfunction "P$3_3B") (pintype "bidirectional"))
      (node (ref "U$4") (pin "SWCLOSED") (pinfunction "SWCLOSE_SWCLOSED") (pintype "bidirectional"))
    )
    (net (code "50") (name "Net-(U1-C1+)") (class "Default")
      (node (ref "C1") (pin "1") (pinfunction "1_1") (pintype "passive"))
      (node (ref "U1") (pin "1") (pinfunction "C1+_1") (pintype "bidirectional"))
    )
    (net (code "51") (name "Net-(U1-C1-)") (class "Default")
      (node (ref "C1") (pin "2") (pinfunction "2_2") (pintype "passive"))
      (node (ref "U1") (pin "3") (pinfunction "C1-_3") (pintype "bidirectional"))
    )
    (net (code "52") (name "Net-(U1-C2+)") (class "Default")
      (node (ref "C2") (pin "1") (pinfunction "1_1") (pintype "passive"))
      (node (ref "U1") (pin "4") (pinfunction "C2+_4") (pintype "bidirectional"))
    )
    (net (code "53") (name "Net-(U1-C2-)") (class "Default")
      (node (ref "C2") (pin "2") (pinfunction "2_2") (pintype "passive"))
      (node (ref "U1") (pin "5") (pinfunction "C2-_5") (pintype "bidirectional"))
    )
    (net (code "54") (name "Net-(U1-V+)") (class "Default")
      (node (ref "C3") (pin "1") (pinfunction "1_1") (pintype "passive"))
      (node (ref "U1") (pin "2") (pinfunction "V+_2") (pintype "bidirectional"))
    )
    (net (code "55") (name "Net-(U1-V-)") (class "Default")
      (node (ref "C4") (pin "1") (pinfunction "1_1") (pintype "passive"))
      (node (ref "U1") (pin "6") (pinfunction "V-_6") (pintype "bidirectional"))
    )
    (net (code "56") (name "R1IN") (class "Default")
      (node (ref "JP3") (pin "2") (pinfunction "2_2") (pintype "passive"))
      (node (ref "U1") (pin "13") (pinfunction "R1IN_13") (pintype "input"))
    )
    (net (code "57") (name "R2IN") (class "Default")
      (node (ref "JP4") (pin "2") (pinfunction "2_2") (pintype "passive"))
      (node (ref "U1") (pin "8") (pinfunction "R2IN_8") (pintype "input"))
    )
    (net (code "58") (name "RELAY1-SIG") (class "Default")
      (node (ref "R154") (pin "2") (pinfunction "2_2") (pintype "passive"))
      (node (ref "U3") (pin "31") (pinfunction "IO38_31") (pintype "bidirectional"))
    )
    (net (code "59") (name "RELAY2-SIG") (class "Default")
      (node (ref "R54") (pin "2") (pinfunction "2_2") (pintype "passive"))
      (node (ref "U3") (pin "32") (pinfunction "IO39_32") (pintype "bidirectional"))
    )
    (net (code "60") (name "RELAY3-SIG") (class "Default")
      (node (ref "R1") (pin "2") (pinfunction "2_2") (pintype "passive"))
      (node (ref "U3") (pin "33") (pinfunction "IO40_33") (pintype "bidirectional"))
    )
    (net (code "61") (name "RELAY4-SIG") (class "Default")
      (node (ref "R3") (pin "2") (pinfunction "2_2") (pintype "passive"))
      (node (ref "U3") (pin "34") (pinfunction "IO41_34") (pintype "bidirectional"))
    )
    (net (code "62") (name "RESET") (class "Default")
      (node (ref "C14") (pin "1") (pinfunction "1_1") (pintype "passive"))
      (node (ref "R16") (pin "1") (pinfunction "1_1") (pintype "passive"))
      (node (ref "RESET") (pin "3") (pinfunction "2_3") (pintype "passive"))
      (node (ref "U3") (pin "3") (pinfunction "EN_3") (pintype "input"))
    )
    (net (code "63") (name "RXD2{slash}IO18") (class "Default")
      (node (ref "U1") (pin "9") (pinfunction "R2OUT_9") (pintype "output"))
      (node (ref "U3") (pin "11") (pinfunction "IO18_11") (pintype "bidirectional"))
    )
    (net (code "64") (name "SHLD") (class "Default")
      (node (ref "CON3") (pin "SHLD1") (pinfunction "SHLD_SHLD1") (pintype "bidirectional"))
      (node (ref "CON3") (pin "SHLD2") (pinfunction "SHLD_SHLD2") (pintype "bidirectional"))
      (node (ref "CON3") (pin "SHLD3") (pinfunction "SHLD_SHLD3") (pintype "bidirectional"))
      (node (ref "CON3") (pin "SHLD4") (pinfunction "SHLD_SHLD4") (pintype "bidirectional"))
      (node (ref "CON3") (pin "SHLD5") (pinfunction "SHLD_SHLD5") (pintype "bidirectional"))
      (node (ref "CON3") (pin "SHLD6") (pinfunction "SHLD_SHLD6") (pintype "bidirectional"))
      (node (ref "CON3") (pin "SHLD7") (pinfunction "SHLD_SHLD7") (pintype "bidirectional"))
      (node (ref "CON3") (pin "SHLD8") (pinfunction "SHLD_SHLD8") (pintype "bidirectional"))
    )
    (net (code "65") (name "T1OUT") (class "Default")
      (node (ref "JP3") (pin "1") (pinfunction "1_1") (pintype "passive"))
      (node (ref "U1") (pin "14") (pinfunction "T1OUT_14") (pintype "output"))
    )
    (net (code "66") (name "T2OUT") (class "Default")
      (node (ref "JP4") (pin "1") (pinfunction "1_1") (pintype "passive"))
      (node (ref "U1") (pin "7") (pinfunction "T2OUT_7") (pintype "output"))
    )
    (net (code "67") (name "TXD2{slash}IO17") (class "Default")
      (node (ref "U1") (pin "10") (pinfunction "T2IN_10") (pintype "input"))
      (node (ref "U3") (pin "10") (pinfunction "IO17_10") (pintype "bidirectional"))
    )
    (net (code "68") (name "TXD{slash}IO43") (class "Default")
      (node (ref "U1") (pin "11") (pinfunction "T1IN_11") (pintype "input"))
      (node (ref "U1") (pin "12") (pinfunction "R1OUT_12") (pintype "output"))
      (node (ref "U3") (pin "37") (pinfunction "TXD0_37") (pintype "bidirectional"))
    )
    (net (code "69") (name "VCC") (class "Default")
      (node (ref "3V3") (pin "2") (pinfunction "2_2") (pintype "passive"))
      (node (ref "5V") (pin "2") (pinfunction "2_2") (pintype "passive"))
      (node (ref "C5") (pin "1") (pinfunction "1_1") (pintype "passive"))
      (node (ref "U1") (pin "16") (pinfunction "VCC_16") (pintype "bidirectional"))
    )
    (net (code "70") (name "unconnected-(U3-IO1-Pad39)") (class "Default")
      (node (ref "U3") (pin "39") (pinfunction "IO1_39") (pintype "bidirectional"))
    )
    (net (code "71") (name "unconnected-(U3-IO2-Pad38)") (class "Default")
      (node (ref "U3") (pin "38") (pinfunction "IO2_38") (pintype "bidirectional"))
    )
    (net (code "72") (name "unconnected-(U3-IO3-Pad15)") (class "Default")
      (node (ref "U3") (pin "15") (pinfunction "IO3_15") (pintype "bidirectional"))
    )
    (net (code "73") (name "unconnected-(U3-IO4-Pad4)") (class "Default")
      (node (ref "U3") (pin "4") (pinfunction "IO4_4") (pintype "bidirectional"))
    )
    (net (code "74") (name "unconnected-(U3-IO5-Pad5)") (class "Default")
      (node (ref "U3") (pin "5") (pinfunction "IO5_5") (pintype "bidirectional"))
    )
    (net (code "75") (name "unconnected-(U3-IO6-Pad6)") (class "Default")
      (node (ref "U3") (pin "6") (pinfunction "IO6_6") (pintype "bidirectional"))
    )
    (net (code "76") (name "unconnected-(U3-IO7-Pad7)") (class "Default")
      (node (ref "U3") (pin "7") (pinfunction "IO7_7") (pintype "bidirectional"))
    )
    (net (code "77") (name "unconnected-(U3-IO8-Pad12)") (class "Default")
      (node (ref "U3") (pin "12") (pinfunction "IO8_12") (pintype "bidirectional"))
    )
    (net (code "78") (name "unconnected-(U3-IO9-Pad17)") (class "Default")
      (node (ref "U3") (pin "17") (pinfunction "IO9_17") (pintype "bidirectional"))
    )
    (net (code "79") (name "unconnected-(U3-IO10-Pad18)") (class "Default")
      (node (ref "U3") (pin "18") (pinfunction "IO10_18") (pintype "bidirectional"))
    )
    (net (code "80") (name "unconnected-(U3-IO11-Pad19)") (class "Default")
      (node (ref "U3") (pin "19") (pinfunction "IO11_19") (pintype "bidirectional"))
    )
    (net (code "81") (name "unconnected-(U3-IO12-Pad20)") (class "Default")
      (node (ref "U3") (pin "20") (pinfunction "IO12_20") (pintype "bidirectional"))
    )
    (net (code "82") (name "unconnected-(U3-IO13-Pad21)") (class "Default")
      (node (ref "U3") (pin "21") (pinfunction "IO13_21") (pintype "bidirectional"))
    )
    (net (code "83") (name "unconnected-(U3-IO14-Pad22)") (class "Default")
      (node (ref "U3") (pin "22") (pinfunction "IO14_22") (pintype "bidirectional"))
    )
    (net (code "84") (name "unconnected-(U3-IO15-Pad8)") (class "Default")
      (node (ref "U3") (pin "8") (pinfunction "IO15_8") (pintype "bidirectional"))
    )
    (net (code "85") (name "unconnected-(U3-IO16-Pad9)") (class "Default")
      (node (ref "U3") (pin "9") (pinfunction "IO16_9") (pintype "bidirectional"))
    )
    (net (code "86") (name "unconnected-(U3-IO21-Pad23)") (class "Default")
      (node (ref "U3") (pin "23") (pinfunction "IO21_23") (pintype "bidirectional"))
    )
    (net (code "87") (name "unconnected-(U3-IO35-Pad28)") (class "Default")
      (node (ref "U3") (pin "28") (pinfunction "IO35_28") (pintype "bidirectional"))
    )
    (net (code "88") (name "unconnected-(U3-IO36-Pad29)") (class "Default")
      (node (ref "U3") (pin "29") (pinfunction "IO36_29") (pintype "bidirectional"))
    )
    (net (code "89") (name "unconnected-(U3-IO37-Pad30)") (class "Default")
      (node (ref "U3") (pin "30") (pinfunction "IO37_30") (pintype "bidirectional"))
    )
    (net (code "90") (name "unconnected-(U3-IO42-Pad35)") (class "Default")
      (node (ref "U3") (pin "35") (pinfunction "IO42_35") (pintype "bidirectional"))
    )
    (net (code "91") (name "unconnected-(U3-IO45-Pad26)") (class "Default")
      (node (ref "U3") (pin "26") (pinfunction "IO45_26") (pintype "bidirectional"))
    )
    (net (code "92") (name "unconnected-(U3-IO46-Pad16)") (class "Default")
      (node (ref "U3") (pin "16") (pinfunction "IO46_16") (pintype "bidirectional"))
    )
    (net (code "93") (name "unconnected-(U3-IO47-Pad24)") (class "Default")
      (node (ref "U3") (pin "24") (pinfunction "IO47_24") (pintype "bidirectional"))
    )
    (net (code "94") (name "unconnected-(U3-IO48-Pad25)") (class "Default")
      (node (ref "U3") (pin "25") (pinfunction "IO48_25") (pintype "bidirectional"))
    )
  )
)
